# Lights.net
KiCad netlist of a schematic drawn in Altium Designer
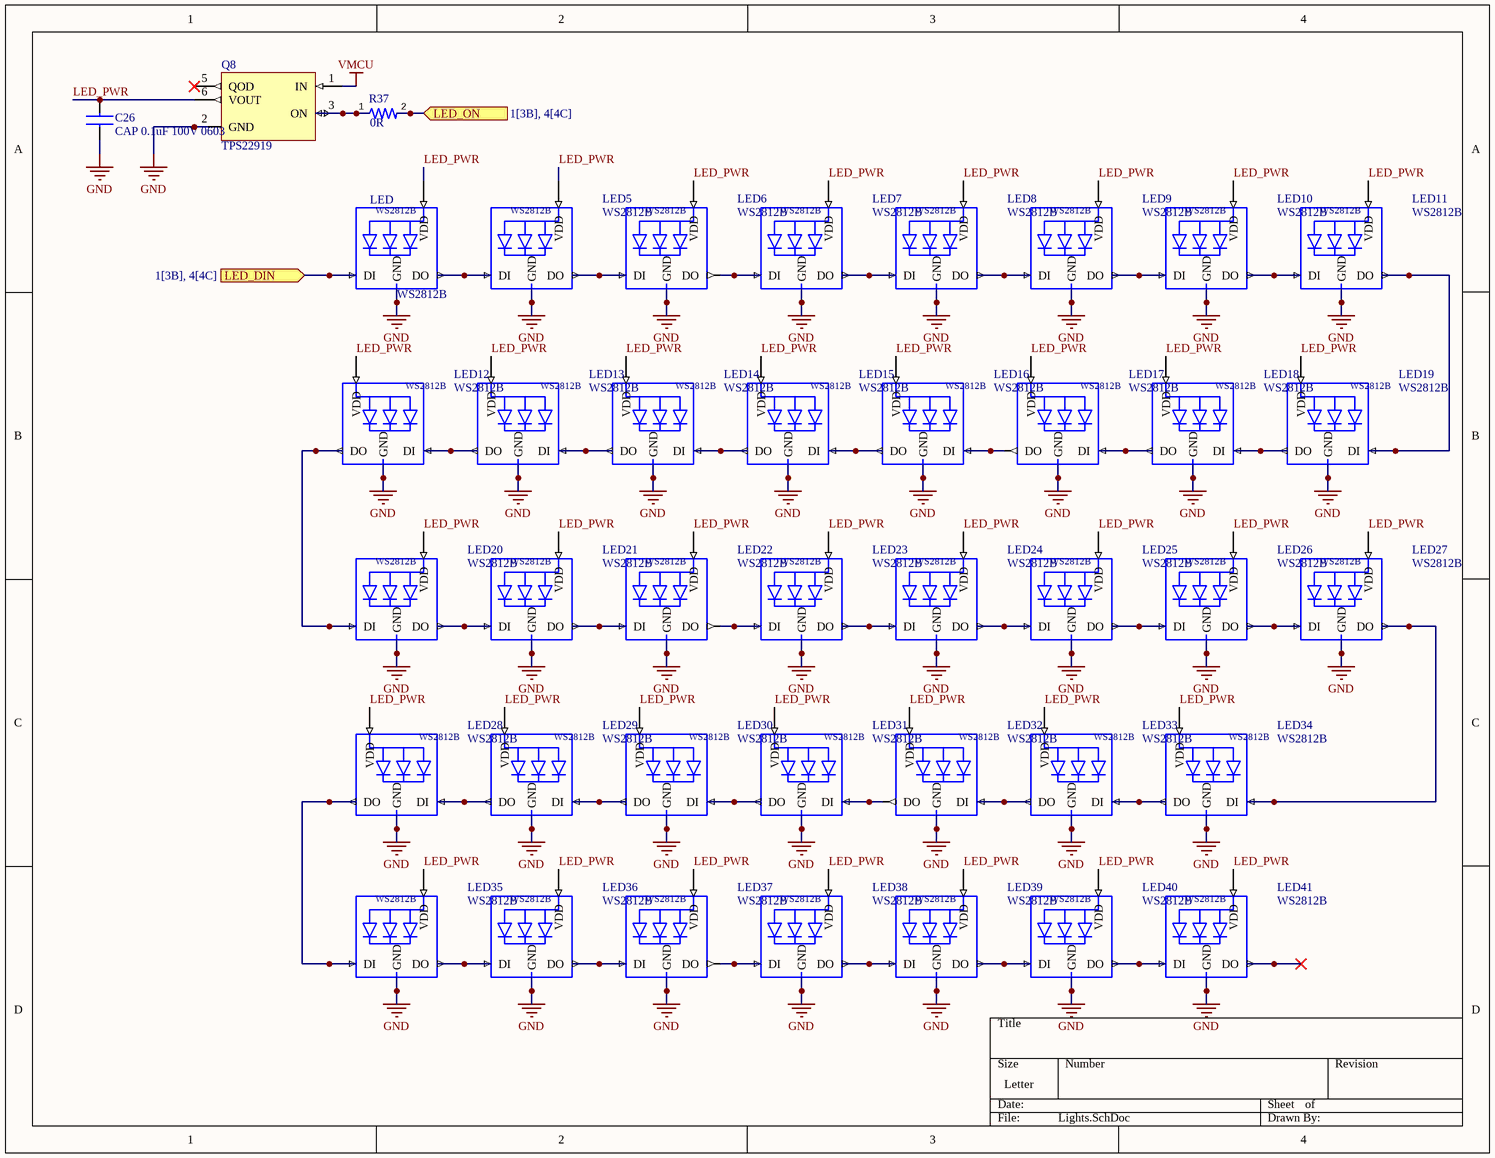
[diagram p0: Lights.SchDoc]

(export (version "E")
  (design (tool "Eeschema 10.0.6"))
  (components
    (comp (ref "C26")
      (value "CAP 0.1uF 100V 0603")
      (footprint "Capacitor 0603")
      (fields
        (field (name "MANUFACTURER") "Murata")
        (field (name "MANUFACTURER PART NUMBER") "GCM188R72A103KA37D")
      )
      (libsource (lib "InsaneIntegratedLib") (part "CAP 0.1uF 100V 0603"))
    )
    (comp (ref "LED")
      (value "WS2812B")
      (footprint "WS2812B")
      (description "Raspberry Pi HAT _40 pin_ Wheeled Robotics Kit")
      (fields (field (name "MF") "SparkFun Electronics"))
      (libsource (lib "Keyboard_parts") (part "WS2812B"))
    )
    (comp (ref "LED5")
      (value "WS2812B")
      (footprint "WS2812B")
      (description "Raspberry Pi HAT _40 pin_ Wheeled Robotics Kit")
      (fields (field (name "MF") "SparkFun Electronics"))
      (libsource (lib "Keyboard_parts") (part "WS2812B"))
    )
    (comp (ref "LED6")
      (value "WS2812B")
      (footprint "WS2812B")
      (description "Raspberry Pi HAT _40 pin_ Wheeled Robotics Kit")
      (fields (field (name "MF") "SparkFun Electronics"))
      (libsource (lib "Keyboard_parts") (part "WS2812B"))
    )
    (comp (ref "LED7")
      (value "WS2812B")
      (footprint "WS2812B")
      (description "Raspberry Pi HAT _40 pin_ Wheeled Robotics Kit")
      (fields (field (name "MF") "SparkFun Electronics"))
      (libsource (lib "Keyboard_parts") (part "WS2812B"))
    )
    (comp (ref "LED8")
      (value "WS2812B")
      (footprint "WS2812B")
      (description "Raspberry Pi HAT _40 pin_ Wheeled Robotics Kit")
      (fields (field (name "MF") "SparkFun Electronics"))
      (libsource (lib "Keyboard_parts") (part "WS2812B"))
    )
    (comp (ref "LED9")
      (value "WS2812B")
      (footprint "WS2812B")
      (description "Raspberry Pi HAT _40 pin_ Wheeled Robotics Kit")
      (fields (field (name "MF") "SparkFun Electronics"))
      (libsource (lib "Keyboard_parts") (part "WS2812B"))
    )
    (comp (ref "LED10")
      (value "WS2812B")
      (footprint "WS2812B")
      (description "Raspberry Pi HAT _40 pin_ Wheeled Robotics Kit")
      (fields (field (name "MF") "SparkFun Electronics"))
      (libsource (lib "Keyboard_parts") (part "WS2812B"))
    )
    (comp (ref "LED11")
      (value "WS2812B")
      (footprint "WS2812B")
      (description "Raspberry Pi HAT _40 pin_ Wheeled Robotics Kit")
      (fields (field (name "MF") "SparkFun Electronics"))
      (libsource (lib "Keyboard_parts") (part "WS2812B"))
    )
    (comp (ref "LED12")
      (value "WS2812B")
      (footprint "WS2812B")
      (description "Raspberry Pi HAT _40 pin_ Wheeled Robotics Kit")
      (fields (field (name "MF") "SparkFun Electronics"))
      (libsource (lib "Keyboard_parts") (part "WS2812B"))
    )
    (comp (ref "LED13")
      (value "WS2812B")
      (footprint "WS2812B")
      (description "Raspberry Pi HAT _40 pin_ Wheeled Robotics Kit")
      (fields (field (name "MF") "SparkFun Electronics"))
      (libsource (lib "Keyboard_parts") (part "WS2812B"))
    )
    (comp (ref "LED14")
      (value "WS2812B")
      (footprint "WS2812B")
      (description "Raspberry Pi HAT _40 pin_ Wheeled Robotics Kit")
      (fields (field (name "MF") "SparkFun Electronics"))
      (libsource (lib "Keyboard_parts") (part "WS2812B"))
    )
    (comp (ref "LED15")
      (value "WS2812B")
      (footprint "WS2812B")
      (description "Raspberry Pi HAT _40 pin_ Wheeled Robotics Kit")
      (fields (field (name "MF") "SparkFun Electronics"))
      (libsource (lib "Keyboard_parts") (part "WS2812B"))
    )
    (comp (ref "LED16")
      (value "WS2812B")
      (footprint "WS2812B")
      (description "Raspberry Pi HAT _40 pin_ Wheeled Robotics Kit")
      (fields (field (name "MF") "SparkFun Electronics"))
      (libsource (lib "Keyboard_parts") (part "WS2812B"))
    )
    (comp (ref "LED17")
      (value "WS2812B")
      (footprint "WS2812B")
      (description "Raspberry Pi HAT _40 pin_ Wheeled Robotics Kit")
      (fields (field (name "MF") "SparkFun Electronics"))
      (libsource (lib "Keyboard_parts") (part "WS2812B"))
    )
    (comp (ref "LED18")
      (value "WS2812B")
      (footprint "WS2812B")
      (description "Raspberry Pi HAT _40 pin_ Wheeled Robotics Kit")
      (fields (field (name "MF") "SparkFun Electronics"))
      (libsource (lib "Keyboard_parts") (part "WS2812B"))
    )
    (comp (ref "LED19")
      (value "WS2812B")
      (footprint "WS2812B")
      (description "Raspberry Pi HAT _40 pin_ Wheeled Robotics Kit")
      (fields (field (name "MF") "SparkFun Electronics"))
      (libsource (lib "Keyboard_parts") (part "WS2812B"))
    )
    (comp (ref "LED20")
      (value "WS2812B")
      (footprint "WS2812B")
      (description "Raspberry Pi HAT _40 pin_ Wheeled Robotics Kit")
      (fields (field (name "MF") "SparkFun Electronics"))
      (libsource (lib "Keyboard_parts") (part "WS2812B"))
    )
    (comp (ref "LED21")
      (value "WS2812B")
      (footprint "WS2812B")
      (description "Raspberry Pi HAT _40 pin_ Wheeled Robotics Kit")
      (fields (field (name "MF") "SparkFun Electronics"))
      (libsource (lib "Keyboard_parts") (part "WS2812B"))
    )
    (comp (ref "LED22")
      (value "WS2812B")
      (footprint "WS2812B")
      (description "Raspberry Pi HAT _40 pin_ Wheeled Robotics Kit")
      (fields (field (name "MF") "SparkFun Electronics"))
      (libsource (lib "Keyboard_parts") (part "WS2812B"))
    )
    (comp (ref "LED23")
      (value "WS2812B")
      (footprint "WS2812B")
      (description "Raspberry Pi HAT _40 pin_ Wheeled Robotics Kit")
      (fields (field (name "MF") "SparkFun Electronics"))
      (libsource (lib "Keyboard_parts") (part "WS2812B"))
    )
    (comp (ref "LED24")
      (value "WS2812B")
      (footprint "WS2812B")
      (description "Raspberry Pi HAT _40 pin_ Wheeled Robotics Kit")
      (fields (field (name "MF") "SparkFun Electronics"))
      (libsource (lib "Keyboard_parts") (part "WS2812B"))
    )
    (comp (ref "LED25")
      (value "WS2812B")
      (footprint "WS2812B")
      (description "Raspberry Pi HAT _40 pin_ Wheeled Robotics Kit")
      (fields (field (name "MF") "SparkFun Electronics"))
      (libsource (lib "Keyboard_parts") (part "WS2812B"))
    )
    (comp (ref "LED26")
      (value "WS2812B")
      (footprint "WS2812B")
      (description "Raspberry Pi HAT _40 pin_ Wheeled Robotics Kit")
      (fields (field (name "MF") "SparkFun Electronics"))
      (libsource (lib "Keyboard_parts") (part "WS2812B"))
    )
    (comp (ref "LED27")
      (value "WS2812B")
      (footprint "WS2812B")
      (description "Raspberry Pi HAT _40 pin_ Wheeled Robotics Kit")
      (fields (field (name "MF") "SparkFun Electronics"))
      (libsource (lib "Keyboard_parts") (part "WS2812B"))
    )
    (comp (ref "LED28")
      (value "WS2812B")
      (footprint "WS2812B")
      (description "Raspberry Pi HAT _40 pin_ Wheeled Robotics Kit")
      (fields (field (name "MF") "SparkFun Electronics"))
      (libsource (lib "Keyboard_parts") (part "WS2812B"))
    )
    (comp (ref "LED29")
      (value "WS2812B")
      (footprint "WS2812B")
      (description "Raspberry Pi HAT _40 pin_ Wheeled Robotics Kit")
      (fields (field (name "MF") "SparkFun Electronics"))
      (libsource (lib "Keyboard_parts") (part "WS2812B"))
    )
    (comp (ref "LED30")
      (value "WS2812B")
      (footprint "WS2812B")
      (description "Raspberry Pi HAT _40 pin_ Wheeled Robotics Kit")
      (fields (field (name "MF") "SparkFun Electronics"))
      (libsource (lib "Keyboard_parts") (part "WS2812B"))
    )
    (comp (ref "LED31")
      (value "WS2812B")
      (footprint "WS2812B")
      (description "Raspberry Pi HAT _40 pin_ Wheeled Robotics Kit")
      (fields (field (name "MF") "SparkFun Electronics"))
      (libsource (lib "Keyboard_parts") (part "WS2812B"))
    )
    (comp (ref "LED32")
      (value "WS2812B")
      (footprint "WS2812B")
      (description "Raspberry Pi HAT _40 pin_ Wheeled Robotics Kit")
      (fields (field (name "MF") "SparkFun Electronics"))
      (libsource (lib "Keyboard_parts") (part "WS2812B"))
    )
    (comp (ref "LED33")
      (value "WS2812B")
      (footprint "WS2812B")
      (description "Raspberry Pi HAT _40 pin_ Wheeled Robotics Kit")
      (fields (field (name "MF") "SparkFun Electronics"))
      (libsource (lib "Keyboard_parts") (part "WS2812B"))
    )
    (comp (ref "LED34")
      (value "WS2812B")
      (footprint "WS2812B")
      (description "Raspberry Pi HAT _40 pin_ Wheeled Robotics Kit")
      (fields (field (name "MF") "SparkFun Electronics"))
      (libsource (lib "Keyboard_parts") (part "WS2812B"))
    )
    (comp (ref "LED35")
      (value "WS2812B")
      (footprint "WS2812B")
      (description "Raspberry Pi HAT _40 pin_ Wheeled Robotics Kit")
      (fields (field (name "MF") "SparkFun Electronics"))
      (libsource (lib "Keyboard_parts") (part "WS2812B"))
    )
    (comp (ref "LED36")
      (value "WS2812B")
      (footprint "WS2812B")
      (description "Raspberry Pi HAT _40 pin_ Wheeled Robotics Kit")
      (fields (field (name "MF") "SparkFun Electronics"))
      (libsource (lib "Keyboard_parts") (part "WS2812B"))
    )
    (comp (ref "LED37")
      (value "WS2812B")
      (footprint "WS2812B")
      (description "Raspberry Pi HAT _40 pin_ Wheeled Robotics Kit")
      (fields (field (name "MF") "SparkFun Electronics"))
      (libsource (lib "Keyboard_parts") (part "WS2812B"))
    )
    (comp (ref "LED38")
      (value "WS2812B")
      (footprint "WS2812B")
      (description "Raspberry Pi HAT _40 pin_ Wheeled Robotics Kit")
      (fields (field (name "MF") "SparkFun Electronics"))
      (libsource (lib "Keyboard_parts") (part "WS2812B"))
    )
    (comp (ref "LED39")
      (value "WS2812B")
      (footprint "WS2812B")
      (description "Raspberry Pi HAT _40 pin_ Wheeled Robotics Kit")
      (fields (field (name "MF") "SparkFun Electronics"))
      (libsource (lib "Keyboard_parts") (part "WS2812B"))
    )
    (comp (ref "LED40")
      (value "WS2812B")
      (footprint "WS2812B")
      (description "Raspberry Pi HAT _40 pin_ Wheeled Robotics Kit")
      (fields (field (name "MF") "SparkFun Electronics"))
      (libsource (lib "Keyboard_parts") (part "WS2812B"))
    )
    (comp (ref "LED41")
      (value "WS2812B")
      (footprint "WS2812B")
      (description "Raspberry Pi HAT _40 pin_ Wheeled Robotics Kit")
      (fields (field (name "MF") "SparkFun Electronics"))
      (libsource (lib "Keyboard_parts") (part "WS2812B"))
    )
    (comp (ref "Q8")
      (value "TPS22919")
      (footprint "TPS22919DCKR - Load SW")
      (description "Buffer/Inverter Based Peripheral Driver, 3A, PDSO6")
      (fields
        (field (name "MANUFACTURER") "Texas Instruments")
        (field (name "MANUFACTURER PART NUMBER") "TPS22919DCKT")
      )
      (libsource (lib "Keyboard_parts") (part "TPS22919"))
    )
    (comp (ref "R37")
      (value "0R")
      (footprint "Resistor 0402")
      (description "Metal Glaze/thick Film, 0.0625W, 0ohm, Surface Mount, 0402")
      (fields
        (field (name "MANUFACTURER") "Yageo")
        (field (name "MANUFACTURER PART NUMBER") "RC0402JR-070RL")
      )
      (libsource (lib "InsaneIntegratedLib") (part "RES 0R 0402"))
    )
  )
  (nets
    (net (code "2") (name "/LED_DIN") (class "Default")
      (node (ref "LED") (pin "4-DIN") (pinfunction "DI_4-DIN") (pintype "input"))
    )
    (net (code "3") (name "/LED_ON") (class "Default")
      (node (ref "R37") (pin "2") (pinfunction "2_2") (pintype "passive"))
    )
    (net (code "4") (name "/LED_PWR") (class "Default")
      (node (ref "C26") (pin "2") (pinfunction "2_2") (pintype "passive"))
      (node (ref "LED") (pin "1-VDD") (pinfunction "VDD_1-VDD") (pintype "input"))
      (node (ref "LED10") (pin "1-VDD") (pinfunction "VDD_1-VDD") (pintype "input"))
      (node (ref "LED11") (pin "1-VDD") (pinfunction "VDD_1-VDD") (pintype "input"))
      (node (ref "LED12") (pin "1-VDD") (pinfunction "VDD_1-VDD") (pintype "input"))
      (node (ref "LED13") (pin "1-VDD") (pinfunction "VDD_1-VDD") (pintype "input"))
      (node (ref "LED14") (pin "1-VDD") (pinfunction "VDD_1-VDD") (pintype "input"))
      (node (ref "LED15") (pin "1-VDD") (pinfunction "VDD_1-VDD") (pintype "input"))
      (node (ref "LED16") (pin "1-VDD") (pinfunction "VDD_1-VDD") (pintype "input"))
      (node (ref "LED17") (pin "1-VDD") (pinfunction "VDD_1-VDD") (pintype "input"))
      (node (ref "LED18") (pin "1-VDD") (pinfunction "VDD_1-VDD") (pintype "input"))
      (node (ref "LED19") (pin "1-VDD") (pinfunction "VDD_1-VDD") (pintype "input"))
      (node (ref "LED20") (pin "1-VDD") (pinfunction "VDD_1-VDD") (pintype "input"))
      (node (ref "LED21") (pin "1-VDD") (pinfunction "VDD_1-VDD") (pintype "input"))
      (node (ref "LED22") (pin "1-VDD") (pinfunction "VDD_1-VDD") (pintype "input"))
      (node (ref "LED23") (pin "1-VDD") (pinfunction "VDD_1-VDD") (pintype "input"))
      (node (ref "LED24") (pin "1-VDD") (pinfunction "VDD_1-VDD") (pintype "input"))
      (node (ref "LED25") (pin "1-VDD") (pinfunction "VDD_1-VDD") (pintype "input"))
      (node (ref "LED26") (pin "1-VDD") (pinfunction "VDD_1-VDD") (pintype "input"))
      (node (ref "LED27") (pin "1-VDD") (pinfunction "VDD_1-VDD") (pintype "input"))
      (node (ref "LED28") (pin "1-VDD") (pinfunction "VDD_1-VDD") (pintype "input"))
      (node (ref "LED29") (pin "1-VDD") (pinfunction "VDD_1-VDD") (pintype "input"))
      (node (ref "LED30") (pin "1-VDD") (pinfunction "VDD_1-VDD") (pintype "input"))
      (node (ref "LED31") (pin "1-VDD") (pinfunction "VDD_1-VDD") (pintype "input"))
      (node (ref "LED32") (pin "1-VDD") (pinfunction "VDD_1-VDD") (pintype "input"))
      (node (ref "LED33") (pin "1-VDD") (pinfunction "VDD_1-VDD") (pintype "input"))
      (node (ref "LED34") (pin "1-VDD") (pinfunction "VDD_1-VDD") (pintype "input"))
      (node (ref "LED35") (pin "1-VDD") (pinfunction "VDD_1-VDD") (pintype "input"))
      (node (ref "LED36") (pin "1-VDD") (pinfunction "VDD_1-VDD") (pintype "input"))
      (node (ref "LED37") (pin "1-VDD") (pinfunction "VDD_1-VDD") (pintype "input"))
      (node (ref "LED38") (pin "1-VDD") (pinfunction "VDD_1-VDD") (pintype "input"))
      (node (ref "LED39") (pin "1-VDD") (pinfunction "VDD_1-VDD") (pintype "input"))
      (node (ref "LED40") (pin "1-VDD") (pinfunction "VDD_1-VDD") (pintype "input"))
      (node (ref "LED41") (pin "1-VDD") (pinfunction "VDD_1-VDD") (pintype "input"))
      (node (ref "LED5") (pin "1-VDD") (pinfunction "VDD_1-VDD") (pintype "input"))
      (node (ref "LED6") (pin "1-VDD") (pinfunction "VDD_1-VDD") (pintype "input"))
      (node (ref "LED7") (pin "1-VDD") (pinfunction "VDD_1-VDD") (pintype "input"))
      (node (ref "LED8") (pin "1-VDD") (pinfunction "VDD_1-VDD") (pintype "input"))
      (node (ref "LED9") (pin "1-VDD") (pinfunction "VDD_1-VDD") (pintype "input"))
      (node (ref "Q8") (pin "6") (pinfunction "VOUT_6") (pintype "output"))
    )
    (net (code "5") (name "GND") (class "Default")
      (node (ref "C26") (pin "1") (pinfunction "1_1") (pintype "passive"))
      (node (ref "LED") (pin "3-GND") (pinfunction "GND_3-GND") (pintype "power_in"))
      (node (ref "LED10") (pin "3-GND") (pinfunction "GND_3-GND") (pintype "power_in"))
      (node (ref "LED11") (pin "3-GND") (pinfunction "GND_3-GND") (pintype "power_in"))
      (node (ref "LED12") (pin "3-GND") (pinfunction "GND_3-GND") (pintype "power_in"))
      (node (ref "LED13") (pin "3-GND") (pinfunction "GND_3-GND") (pintype "power_in"))
      (node (ref "LED14") (pin "3-GND") (pinfunction "GND_3-GND") (pintype "power_in"))
      (node (ref "LED15") (pin "3-GND") (pinfunction "GND_3-GND") (pintype "power_in"))
      (node (ref "LED16") (pin "3-GND") (pinfunction "GND_3-GND") (pintype "power_in"))
      (node (ref "LED17") (pin "3-GND") (pinfunction "GND_3-GND") (pintype "power_in"))
      (node (ref "LED18") (pin "3-GND") (pinfunction "GND_3-GND") (pintype "power_in"))
      (node (ref "LED19") (pin "3-GND") (pinfunction "GND_3-GND") (pintype "power_in"))
      (node (ref "LED20") (pin "3-GND") (pinfunction "GND_3-GND") (pintype "power_in"))
      (node (ref "LED21") (pin "3-GND") (pinfunction "GND_3-GND") (pintype "power_in"))
      (node (ref "LED22") (pin "3-GND") (pinfunction "GND_3-GND") (pintype "power_in"))
      (node (ref "LED23") (pin "3-GND") (pinfunction "GND_3-GND") (pintype "power_in"))
      (node (ref "LED24") (pin "3-GND") (pinfunction "GND_3-GND") (pintype "power_in"))
      (node (ref "LED25") (pin "3-GND") (pinfunction "GND_3-GND") (pintype "power_in"))
      (node (ref "LED26") (pin "3-GND") (pinfunction "GND_3-GND") (pintype "power_in"))
      (node (ref "LED27") (pin "3-GND") (pinfunction "GND_3-GND") (pintype "power_in"))
      (node (ref "LED28") (pin "3-GND") (pinfunction "GND_3-GND") (pintype "power_in"))
      (node (ref "LED29") (pin "3-GND") (pinfunction "GND_3-GND") (pintype "power_in"))
      (node (ref "LED30") (pin "3-GND") (pinfunction "GND_3-GND") (pintype "power_in"))
      (node (ref "LED31") (pin "3-GND") (pinfunction "GND_3-GND") (pintype "power_in"))
      (node (ref "LED32") (pin "3-GND") (pinfunction "GND_3-GND") (pintype "power_in"))
      (node (ref "LED33") (pin "3-GND") (pinfunction "GND_3-GND") (pintype "power_in"))
      (node (ref "LED34") (pin "3-GND") (pinfunction "GND_3-GND") (pintype "power_in"))
      (node (ref "LED35") (pin "3-GND") (pinfunction "GND_3-GND") (pintype "power_in"))
      (node (ref "LED36") (pin "3-GND") (pinfunction "GND_3-GND") (pintype "power_in"))
      (node (ref "LED37") (pin "3-GND") (pinfunction "GND_3-GND") (pintype "power_in"))
      (node (ref "LED38") (pin "3-GND") (pinfunction "GND_3-GND") (pintype "power_in"))
      (node (ref "LED39") (pin "3-GND") (pinfunction "GND_3-GND") (pintype "power_in"))
      (node (ref "LED40") (pin "3-GND") (pinfunction "GND_3-GND") (pintype "power_in"))
      (node (ref "LED41") (pin "3-GND") (pinfunction "GND_3-GND") (pintype "power_in"))
      (node (ref "LED5") (pin "3-GND") (pinfunction "GND_3-GND") (pintype "power_in"))
      (node (ref "LED6") (pin "3-GND") (pinfunction "GND_3-GND") (pintype "power_in"))
      (node (ref "LED7") (pin "3-GND") (pinfunction "GND_3-GND") (pintype "power_in"))
      (node (ref "LED8") (pin "3-GND") (pinfunction "GND_3-GND") (pintype "power_in"))
      (node (ref "LED9") (pin "3-GND") (pinfunction "GND_3-GND") (pintype "power_in"))
      (node (ref "Q8") (pin "2") (pinfunction "GND_2") (pintype "passive"))
    )
    (net (code "6") (name "Net-(LED-DO)") (class "Default")
      (node (ref "LED") (pin "2-DOUT") (pinfunction "DO_2-DOUT") (pintype "output"))
      (node (ref "LED5") (pin "4-DIN") (pinfunction "DI_4-DIN") (pintype "input"))
    )
    (net (code "7") (name "Net-(LED5-DO)") (class "Default")
      (node (ref "LED5") (pin "2-DOUT") (pinfunction "DO_2-DOUT") (pintype "output"))
      (node (ref "LED6") (pin "4-DIN") (pinfunction "DI_4-DIN") (pintype "input"))
    )
    (net (code "8") (name "Net-(LED6-DO)") (class "Default")
      (node (ref "LED6") (pin "2-DOUT") (pinfunction "DO_2-DOUT") (pintype "output"))
      (node (ref "LED7") (pin "4-DIN") (pinfunction "DI_4-DIN") (pintype "input"))
    )
    (net (code "9") (name "Net-(LED7-DO)") (class "Default")
      (node (ref "LED7") (pin "2-DOUT") (pinfunction "DO_2-DOUT") (pintype "output"))
      (node (ref "LED8") (pin "4-DIN") (pinfunction "DI_4-DIN") (pintype "input"))
    )
    (net (code "10") (name "Net-(LED8-DO)") (class "Default")
      (node (ref "LED8") (pin "2-DOUT") (pinfunction "DO_2-DOUT") (pintype "output"))
      (node (ref "LED9") (pin "4-DIN") (pinfunction "DI_4-DIN") (pintype "input"))
    )
    (net (code "11") (name "Net-(LED10-DI)") (class "Default")
      (node (ref "LED10") (pin "4-DIN") (pinfunction "DI_4-DIN") (pintype "input"))
      (node (ref "LED9") (pin "2-DOUT") (pinfunction "DO_2-DOUT") (pintype "output"))
    )
    (net (code "12") (name "Net-(LED10-DO)") (class "Default")
      (node (ref "LED10") (pin "2-DOUT") (pinfunction "DO_2-DOUT") (pintype "output"))
      (node (ref "LED11") (pin "4-DIN") (pinfunction "DI_4-DIN") (pintype "input"))
    )
    (net (code "13") (name "Net-(LED11-DO)") (class "Default")
      (node (ref "LED11") (pin "2-DOUT") (pinfunction "DO_2-DOUT") (pintype "output"))
      (node (ref "LED19") (pin "4-DIN") (pinfunction "DI_4-DIN") (pintype "input"))
    )
    (net (code "14") (name "Net-(LED12-DI)") (class "Default")
      (node (ref "LED12") (pin "4-DIN") (pinfunction "DI_4-DIN") (pintype "input"))
      (node (ref "LED13") (pin "2-DOUT") (pinfunction "DO_2-DOUT") (pintype "output"))
    )
    (net (code "15") (name "Net-(LED12-DO)") (class "Default")
      (node (ref "LED12") (pin "2-DOUT") (pinfunction "DO_2-DOUT") (pintype "output"))
      (node (ref "LED20") (pin "4-DIN") (pinfunction "DI_4-DIN") (pintype "input"))
    )
    (net (code "16") (name "Net-(LED13-DI)") (class "Default")
      (node (ref "LED13") (pin "4-DIN") (pinfunction "DI_4-DIN") (pintype "input"))
      (node (ref "LED14") (pin "2-DOUT") (pinfunction "DO_2-DOUT") (pintype "output"))
    )
    (net (code "17") (name "Net-(LED14-DI)") (class "Default")
      (node (ref "LED14") (pin "4-DIN") (pinfunction "DI_4-DIN") (pintype "input"))
      (node (ref "LED15") (pin "2-DOUT") (pinfunction "DO_2-DOUT") (pintype "output"))
    )
    (net (code "18") (name "Net-(LED15-DI)") (class "Default")
      (node (ref "LED15") (pin "4-DIN") (pinfunction "DI_4-DIN") (pintype "input"))
      (node (ref "LED16") (pin "2-DOUT") (pinfunction "DO_2-DOUT") (pintype "output"))
    )
    (net (code "19") (name "Net-(LED16-DI)") (class "Default")
      (node (ref "LED16") (pin "4-DIN") (pinfunction "DI_4-DIN") (pintype "input"))
      (node (ref "LED17") (pin "2-DOUT") (pinfunction "DO_2-DOUT") (pintype "output"))
    )
    (net (code "20") (name "Net-(LED17-DI)") (class "Default")
      (node (ref "LED17") (pin "4-DIN") (pinfunction "DI_4-DIN") (pintype "input"))
      (node (ref "LED18") (pin "2-DOUT") (pinfunction "DO_2-DOUT") (pintype "output"))
    )
    (net (code "21") (name "Net-(LED18-DI)") (class "Default")
      (node (ref "LED18") (pin "4-DIN") (pinfunction "DI_4-DIN") (pintype "input"))
      (node (ref "LED19") (pin "2-DOUT") (pinfunction "DO_2-DOUT") (pintype "output"))
    )
    (net (code "22") (name "Net-(LED20-DO)") (class "Default")
      (node (ref "LED20") (pin "2-DOUT") (pinfunction "DO_2-DOUT") (pintype "output"))
      (node (ref "LED21") (pin "4-DIN") (pinfunction "DI_4-DIN") (pintype "input"))
    )
    (net (code "23") (name "Net-(LED21-DO)") (class "Default")
      (node (ref "LED21") (pin "2-DOUT") (pinfunction "DO_2-DOUT") (pintype "output"))
      (node (ref "LED22") (pin "4-DIN") (pinfunction "DI_4-DIN") (pintype "input"))
    )
    (net (code "24") (name "Net-(LED22-DO)") (class "Default")
      (node (ref "LED22") (pin "2-DOUT") (pinfunction "DO_2-DOUT") (pintype "output"))
      (node (ref "LED23") (pin "4-DIN") (pinfunction "DI_4-DIN") (pintype "input"))
    )
    (net (code "25") (name "Net-(LED23-DO)") (class "Default")
      (node (ref "LED23") (pin "2-DOUT") (pinfunction "DO_2-DOUT") (pintype "output"))
      (node (ref "LED24") (pin "4-DIN") (pinfunction "DI_4-DIN") (pintype "input"))
    )
    (net (code "26") (name "Net-(LED24-DO)") (class "Default")
      (node (ref "LED24") (pin "2-DOUT") (pinfunction "DO_2-DOUT") (pintype "output"))
      (node (ref "LED25") (pin "4-DIN") (pinfunction "DI_4-DIN") (pintype "input"))
    )
    (net (code "27") (name "Net-(LED25-DO)") (class "Default")
      (node (ref "LED25") (pin "2-DOUT") (pinfunction "DO_2-DOUT") (pintype "output"))
      (node (ref "LED26") (pin "4-DIN") (pinfunction "DI_4-DIN") (pintype "input"))
    )
    (net (code "28") (name "Net-(LED26-DO)") (class "Default")
      (node (ref "LED26") (pin "2-DOUT") (pinfunction "DO_2-DOUT") (pintype "output"))
      (node (ref "LED27") (pin "4-DIN") (pinfunction "DI_4-DIN") (pintype "input"))
    )
    (net (code "29") (name "Net-(LED27-DO)") (class "Default")
      (node (ref "LED27") (pin "2-DOUT") (pinfunction "DO_2-DOUT") (pintype "output"))
      (node (ref "LED34") (pin "4-DIN") (pinfunction "DI_4-DIN") (pintype "input"))
    )
    (net (code "30") (name "Net-(LED28-DI)") (class "Default")
      (node (ref "LED28") (pin "4-DIN") (pinfunction "DI_4-DIN") (pintype "input"))
      (node (ref "LED29") (pin "2-DOUT") (pinfunction "DO_2-DOUT") (pintype "output"))
    )
    (net (code "31") (name "Net-(LED28-DO)") (class "Default")
      (node (ref "LED28") (pin "2-DOUT") (pinfunction "DO_2-DOUT") (pintype "output"))
      (node (ref "LED35") (pin "4-DIN") (pinfunction "DI_4-DIN") (pintype "input"))
    )
    (net (code "32") (name "Net-(LED29-DI)") (class "Default")
      (node (ref "LED29") (pin "4-DIN") (pinfunction "DI_4-DIN") (pintype "input"))
      (node (ref "LED30") (pin "2-DOUT") (pinfunction "DO_2-DOUT") (pintype "output"))
    )
    (net (code "33") (name "Net-(LED30-DI)") (class "Default")
      (node (ref "LED30") (pin "4-DIN") (pinfunction "DI_4-DIN") (pintype "input"))
      (node (ref "LED31") (pin "2-DOUT") (pinfunction "DO_2-DOUT") (pintype "output"))
    )
    (net (code "34") (name "Net-(LED31-DI)") (class "Default")
      (node (ref "LED31") (pin "4-DIN") (pinfunction "DI_4-DIN") (pintype "input"))
      (node (ref "LED32") (pin "2-DOUT") (pinfunction "DO_2-DOUT") (pintype "output"))
    )
    (net (code "35") (name "Net-(LED32-DI)") (class "Default")
      (node (ref "LED32") (pin "4-DIN") (pinfunction "DI_4-DIN") (pintype "input"))
      (node (ref "LED33") (pin "2-DOUT") (pinfunction "DO_2-DOUT") (pintype "output"))
    )
    (net (code "36") (name "Net-(LED33-DI)") (class "Default")
      (node (ref "LED33") (pin "4-DIN") (pinfunction "DI_4-DIN") (pintype "input"))
      (node (ref "LED34") (pin "2-DOUT") (pinfunction "DO_2-DOUT") (pintype "output"))
    )
    (net (code "37") (name "Net-(LED35-DO)") (class "Default")
      (node (ref "LED35") (pin "2-DOUT") (pinfunction "DO_2-DOUT") (pintype "output"))
      (node (ref "LED36") (pin "4-DIN") (pinfunction "DI_4-DIN") (pintype "input"))
    )
    (net (code "38") (name "Net-(LED36-DO)") (class "Default")
      (node (ref "LED36") (pin "2-DOUT") (pinfunction "DO_2-DOUT") (pintype "output"))
      (node (ref "LED37") (pin "4-DIN") (pinfunction "DI_4-DIN") (pintype "input"))
    )
    (net (code "39") (name "Net-(LED37-DO)") (class "Default")
      (node (ref "LED37") (pin "2-DOUT") (pinfunction "DO_2-DOUT") (pintype "output"))
      (node (ref "LED38") (pin "4-DIN") (pinfunction "DI_4-DIN") (pintype "input"))
    )
    (net (code "40") (name "Net-(LED38-DO)") (class "Default")
      (node (ref "LED38") (pin "2-DOUT") (pinfunction "DO_2-DOUT") (pintype "output"))
      (node (ref "LED39") (pin "4-DIN") (pinfunction "DI_4-DIN") (pintype "input"))
    )
    (net (code "41") (name "Net-(LED39-DO)") (class "Default")
      (node (ref "LED39") (pin "2-DOUT") (pinfunction "DO_2-DOUT") (pintype "output"))
      (node (ref "LED40") (pin "4-DIN") (pinfunction "DI_4-DIN") (pintype "input"))
    )
    (net (code "42") (name "Net-(LED40-DO)") (class "Default")
      (node (ref "LED40") (pin "2-DOUT") (pinfunction "DO_2-DOUT") (pintype "output"))
      (node (ref "LED41") (pin "4-DIN") (pinfunction "DI_4-DIN") (pintype "input"))
    )
    (net (code "43") (name "Net-(Q8-ON)") (class "Default")
      (node (ref "Q8") (pin "3") (pinfunction "ON_3") (pintype "bidirectional"))
      (node (ref "R37") (pin "1") (pinfunction "1_1") (pintype "passive"))
    )
    (net (code "44") (name "VMCU") (class "Default")
      (node (ref "Q8") (pin "1") (pinfunction "IN_1") (pintype "input"))
    )
    (net (code "45") (name "unconnected-(LED41-DO-Pad2-DOUT)") (class "Default")
      (node (ref "LED41") (pin "2-DOUT") (pinfunction "DO_2-DOUT") (pintype "output+no_connect"))
    )
    (net (code "46") (name "unconnected-(Q8-QOD-Pad5)") (class "Default")
      (node (ref "Q8") (pin "5") (pinfunction "QOD_5") (pintype "output+no_connect"))
    )
  )
)
